# modulesShield_v1.net
KiCad netlist of a schematic drawn in EAGLE
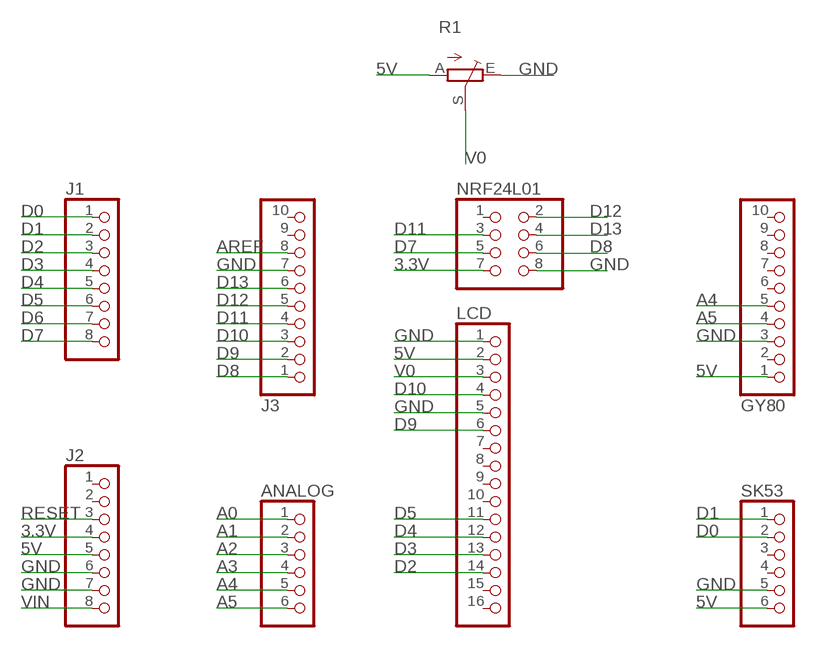
[diagram p0: schematic, sheet 1]

(export (version "E")
  (design (tool "Eeschema 10.0.6"))
  (components
    (comp (ref "ANALOG")
      (value "PINHD-1X6")
      (footprint "eagle-import:1X06")
      (libsource (lib "eagle-import") (part "PINHD-1X6"))
    )
    (comp (ref "GY80")
      (value "PINHD-1X10TH")
      (footprint "eagle-import:1X10-TH")
      (libsource (lib "eagle-import") (part "PINHD-1X10TH"))
    )
    (comp (ref "J1")
      (value "PINHD-1X8TH")
      (footprint "eagle-import:1X08-TH")
      (libsource (lib "eagle-import") (part "PINHD-1X8TH"))
    )
    (comp (ref "J2")
      (value "PINHD-1X8TH")
      (footprint "eagle-import:1X08-TH")
      (libsource (lib "eagle-import") (part "PINHD-1X8TH"))
    )
    (comp (ref "J3")
      (value "PINHD-1X10TH")
      (footprint "eagle-import:1X10-TH")
      (libsource (lib "eagle-import") (part "PINHD-1X10TH"))
    )
    (comp (ref "LCD")
      (value "PINHD-1X16")
      (footprint "eagle-import:1X16")
      (libsource (lib "eagle-import") (part "PINHD-1X16"))
    )
    (comp (ref "NRF24L01")
      (value "PINHD-2X4")
      (footprint "eagle-import:2X04")
      (libsource (lib "eagle-import") (part "PINHD-2X4"))
    )
    (comp (ref "R1")
      (value "TRIM_EU-CA6V")
      (footprint "eagle-import:CA6V")
      (libsource (lib "eagle-import") (part "TRIM_EU-CA6V"))
    )
    (comp (ref "SK53")
      (value "PINHD-1X6")
      (footprint "eagle-import:1X06")
      (libsource (lib "eagle-import") (part "PINHD-1X6"))
    )
  )
  (nets
    (net (code "1") (name "/3.3V") (class "Default")
      (node (ref "J2") (pin "4") (pinfunction "4_4") (pintype "passive"))
      (node (ref "NRF24L01") (pin "7") (pinfunction "7_7") (pintype "passive"))
    )
    (net (code "2") (name "/5V") (class "Default")
      (node (ref "GY80") (pin "1") (pinfunction "1_1") (pintype "passive"))
      (node (ref "J2") (pin "5") (pinfunction "5_5") (pintype "passive"))
      (node (ref "LCD") (pin "2") (pinfunction "2_2") (pintype "passive"))
      (node (ref "R1") (pin "A") (pinfunction "A_A") (pintype "passive"))
      (node (ref "SK53") (pin "6") (pinfunction "6_6") (pintype "passive"))
    )
    (net (code "3") (name "/A0") (class "Default")
      (node (ref "ANALOG") (pin "1") (pinfunction "1_1") (pintype "passive"))
    )
    (net (code "4") (name "/A1") (class "Default")
      (node (ref "ANALOG") (pin "2") (pinfunction "2_2") (pintype "passive"))
    )
    (net (code "5") (name "/A2") (class "Default")
      (node (ref "ANALOG") (pin "3") (pinfunction "3_3") (pintype "passive"))
    )
    (net (code "6") (name "/A3") (class "Default")
      (node (ref "ANALOG") (pin "4") (pinfunction "4_4") (pintype "passive"))
    )
    (net (code "7") (name "/A4") (class "Default")
      (node (ref "ANALOG") (pin "5") (pinfunction "5_5") (pintype "passive"))
      (node (ref "GY80") (pin "5") (pinfunction "5_5") (pintype "passive"))
    )
    (net (code "8") (name "/A5") (class "Default")
      (node (ref "ANALOG") (pin "6") (pinfunction "6_6") (pintype "passive"))
      (node (ref "GY80") (pin "4") (pinfunction "4_4") (pintype "passive"))
    )
    (net (code "9") (name "/AREF") (class "Default")
      (node (ref "J3") (pin "8") (pinfunction "8_8") (pintype "passive"))
    )
    (net (code "10") (name "/D0") (class "Default")
      (node (ref "J1") (pin "1") (pinfunction "1_1") (pintype "passive"))
      (node (ref "SK53") (pin "2") (pinfunction "2_2") (pintype "passive"))
    )
    (net (code "11") (name "/D1") (class "Default")
      (node (ref "J1") (pin "2") (pinfunction "2_2") (pintype "passive"))
      (node (ref "SK53") (pin "1") (pinfunction "1_1") (pintype "passive"))
    )
    (net (code "12") (name "/D2") (class "Default")
      (node (ref "J1") (pin "3") (pinfunction "3_3") (pintype "passive"))
      (node (ref "LCD") (pin "14") (pinfunction "14_14") (pintype "passive"))
    )
    (net (code "13") (name "/D3") (class "Default")
      (node (ref "J1") (pin "4") (pinfunction "4_4") (pintype "passive"))
      (node (ref "LCD") (pin "13") (pinfunction "13_13") (pintype "passive"))
    )
    (net (code "14") (name "/D4") (class "Default")
      (node (ref "J1") (pin "5") (pinfunction "5_5") (pintype "passive"))
      (node (ref "LCD") (pin "12") (pinfunction "12_12") (pintype "passive"))
    )
    (net (code "15") (name "/D5") (class "Default")
      (node (ref "J1") (pin "6") (pinfunction "6_6") (pintype "passive"))
      (node (ref "LCD") (pin "11") (pinfunction "11_11") (pintype "passive"))
    )
    (net (code "16") (name "/D6") (class "Default")
      (node (ref "J1") (pin "7") (pinfunction "7_7") (pintype "passive"))
    )
    (net (code "17") (name "/D7") (class "Default")
      (node (ref "J1") (pin "8") (pinfunction "8_8") (pintype "passive"))
      (node (ref "NRF24L01") (pin "5") (pinfunction "5_5") (pintype "passive"))
    )
    (net (code "18") (name "/D8") (class "Default")
      (node (ref "J3") (pin "1") (pinfunction "1_1") (pintype "passive"))
      (node (ref "NRF24L01") (pin "6") (pinfunction "6_6") (pintype "passive"))
    )
    (net (code "19") (name "/D9") (class "Default")
      (node (ref "J3") (pin "2") (pinfunction "2_2") (pintype "passive"))
      (node (ref "LCD") (pin "6") (pinfunction "6_6") (pintype "passive"))
    )
    (net (code "20") (name "/D10") (class "Default")
      (node (ref "J3") (pin "3") (pinfunction "3_3") (pintype "passive"))
      (node (ref "LCD") (pin "4") (pinfunction "4_4") (pintype "passive"))
    )
    (net (code "21") (name "/D11") (class "Default")
      (node (ref "J3") (pin "4") (pinfunction "4_4") (pintype "passive"))
      (node (ref "NRF24L01") (pin "3") (pinfunction "3_3") (pintype "passive"))
    )
    (net (code "22") (name "/D12") (class "Default")
      (node (ref "J3") (pin "5") (pinfunction "5_5") (pintype "passive"))
      (node (ref "NRF24L01") (pin "2") (pinfunction "2_2") (pintype "passive"))
    )
    (net (code "23") (name "/D13") (class "Default")
      (node (ref "J3") (pin "6") (pinfunction "6_6") (pintype "passive"))
      (node (ref "NRF24L01") (pin "4") (pinfunction "4_4") (pintype "passive"))
    )
    (net (code "24") (name "/GND") (class "Default")
      (node (ref "GY80") (pin "3") (pinfunction "3_3") (pintype "passive"))
      (node (ref "J2") (pin "6") (pinfunction "6_6") (pintype "passive"))
      (node (ref "J2") (pin "7") (pinfunction "7_7") (pintype "passive"))
      (node (ref "J3") (pin "7") (pinfunction "7_7") (pintype "passive"))
      (node (ref "LCD") (pin "1") (pinfunction "1_1") (pintype "passive"))
      (node (ref "LCD") (pin "5") (pinfunction "5_5") (pintype "passive"))
      (node (ref "NRF24L01") (pin "8") (pinfunction "8_8") (pintype "passive"))
      (node (ref "R1") (pin "E") (pinfunction "E_E") (pintype "passive"))
      (node (ref "SK53") (pin "5") (pinfunction "5_5") (pintype "passive"))
    )
    (net (code "25") (name "/RESET") (class "Default")
      (node (ref "J2") (pin "3") (pinfunction "3_3") (pintype "passive"))
    )
    (net (code "26") (name "/V0") (class "Default")
      (node (ref "LCD") (pin "3") (pinfunction "3_3") (pintype "passive"))
      (node (ref "R1") (pin "S") (pinfunction "S_S") (pintype "passive"))
    )
    (net (code "27") (name "/VIN") (class "Default")
      (node (ref "J2") (pin "8") (pinfunction "8_8") (pintype "passive"))
    )
    (net (code "28") (name "unconnected-(GY80-Pad2)") (class "Default")
      (node (ref "GY80") (pin "2") (pinfunction "2_2") (pintype "passive"))
    )
    (net (code "29") (name "unconnected-(GY80-Pad6)") (class "Default")
      (node (ref "GY80") (pin "6") (pinfunction "6_6") (pintype "passive"))
    )
    (net (code "30") (name "unconnected-(GY80-Pad7)") (class "Default")
      (node (ref "GY80") (pin "7") (pinfunction "7_7") (pintype "passive"))
    )
    (net (code "31") (name "unconnected-(GY80-Pad8)") (class "Default")
      (node (ref "GY80") (pin "8") (pinfunction "8_8") (pintype "passive"))
    )
    (net (code "32") (name "unconnected-(GY80-Pad9)") (class "Default")
      (node (ref "GY80") (pin "9") (pinfunction "9_9") (pintype "passive"))
    )
    (net (code "33") (name "unconnected-(GY80-Pad10)") (class "Default")
      (node (ref "GY80") (pin "10") (pinfunction "10_10") (pintype "passive"))
    )
    (net (code "34") (name "unconnected-(J2-Pad1)") (class "Default")
      (node (ref "J2") (pin "1") (pinfunction "1_1") (pintype "passive"))
    )
    (net (code "35") (name "unconnected-(J2-Pad2)") (class "Default")
      (node (ref "J2") (pin "2") (pinfunction "2_2") (pintype "passive"))
    )
    (net (code "36") (name "unconnected-(J3-Pad9)") (class "Default")
      (node (ref "J3") (pin "9") (pinfunction "9_9") (pintype "passive"))
    )
    (net (code "37") (name "unconnected-(J3-Pad10)") (class "Default")
      (node (ref "J3") (pin "10") (pinfunction "10_10") (pintype "passive"))
    )
    (net (code "38") (name "unconnected-(LCD-Pad7)") (class "Default")
      (node (ref "LCD") (pin "7") (pinfunction "7_7") (pintype "passive"))
    )
    (net (code "39") (name "unconnected-(LCD-Pad8)") (class "Default")
      (node (ref "LCD") (pin "8") (pinfunction "8_8") (pintype "passive"))
    )
    (net (code "40") (name "unconnected-(LCD-Pad9)") (class "Default")
      (node (ref "LCD") (pin "9") (pinfunction "9_9") (pintype "passive"))
    )
    (net (code "41") (name "unconnected-(LCD-Pad10)") (class "Default")
      (node (ref "LCD") (pin "10") (pinfunction "10_10") (pintype "passive"))
    )
    (net (code "42") (name "unconnected-(LCD-Pad15)") (class "Default")
      (node (ref "LCD") (pin "15") (pinfunction "15_15") (pintype "passive"))
    )
    (net (code "43") (name "unconnected-(LCD-Pad16)") (class "Default")
      (node (ref "LCD") (pin "16") (pinfunction "16_16") (pintype "passive"))
    )
    (net (code "44") (name "unconnected-(NRF24L01-Pad1)") (class "Default")
      (node (ref "NRF24L01") (pin "1") (pinfunction "1_1") (pintype "passive"))
    )
    (net (code "45") (name "unconnected-(SK53-Pad3)") (class "Default")
      (node (ref "SK53") (pin "3") (pinfunction "3_3") (pintype "passive"))
    )
    (net (code "46") (name "unconnected-(SK53-Pad4)") (class "Default")
      (node (ref "SK53") (pin "4") (pinfunction "4_4") (pintype "passive"))
    )
  )
)
